# 88E1512_1000M_SFP.net
KiCad netlist of a schematic drawn in Altium Designer
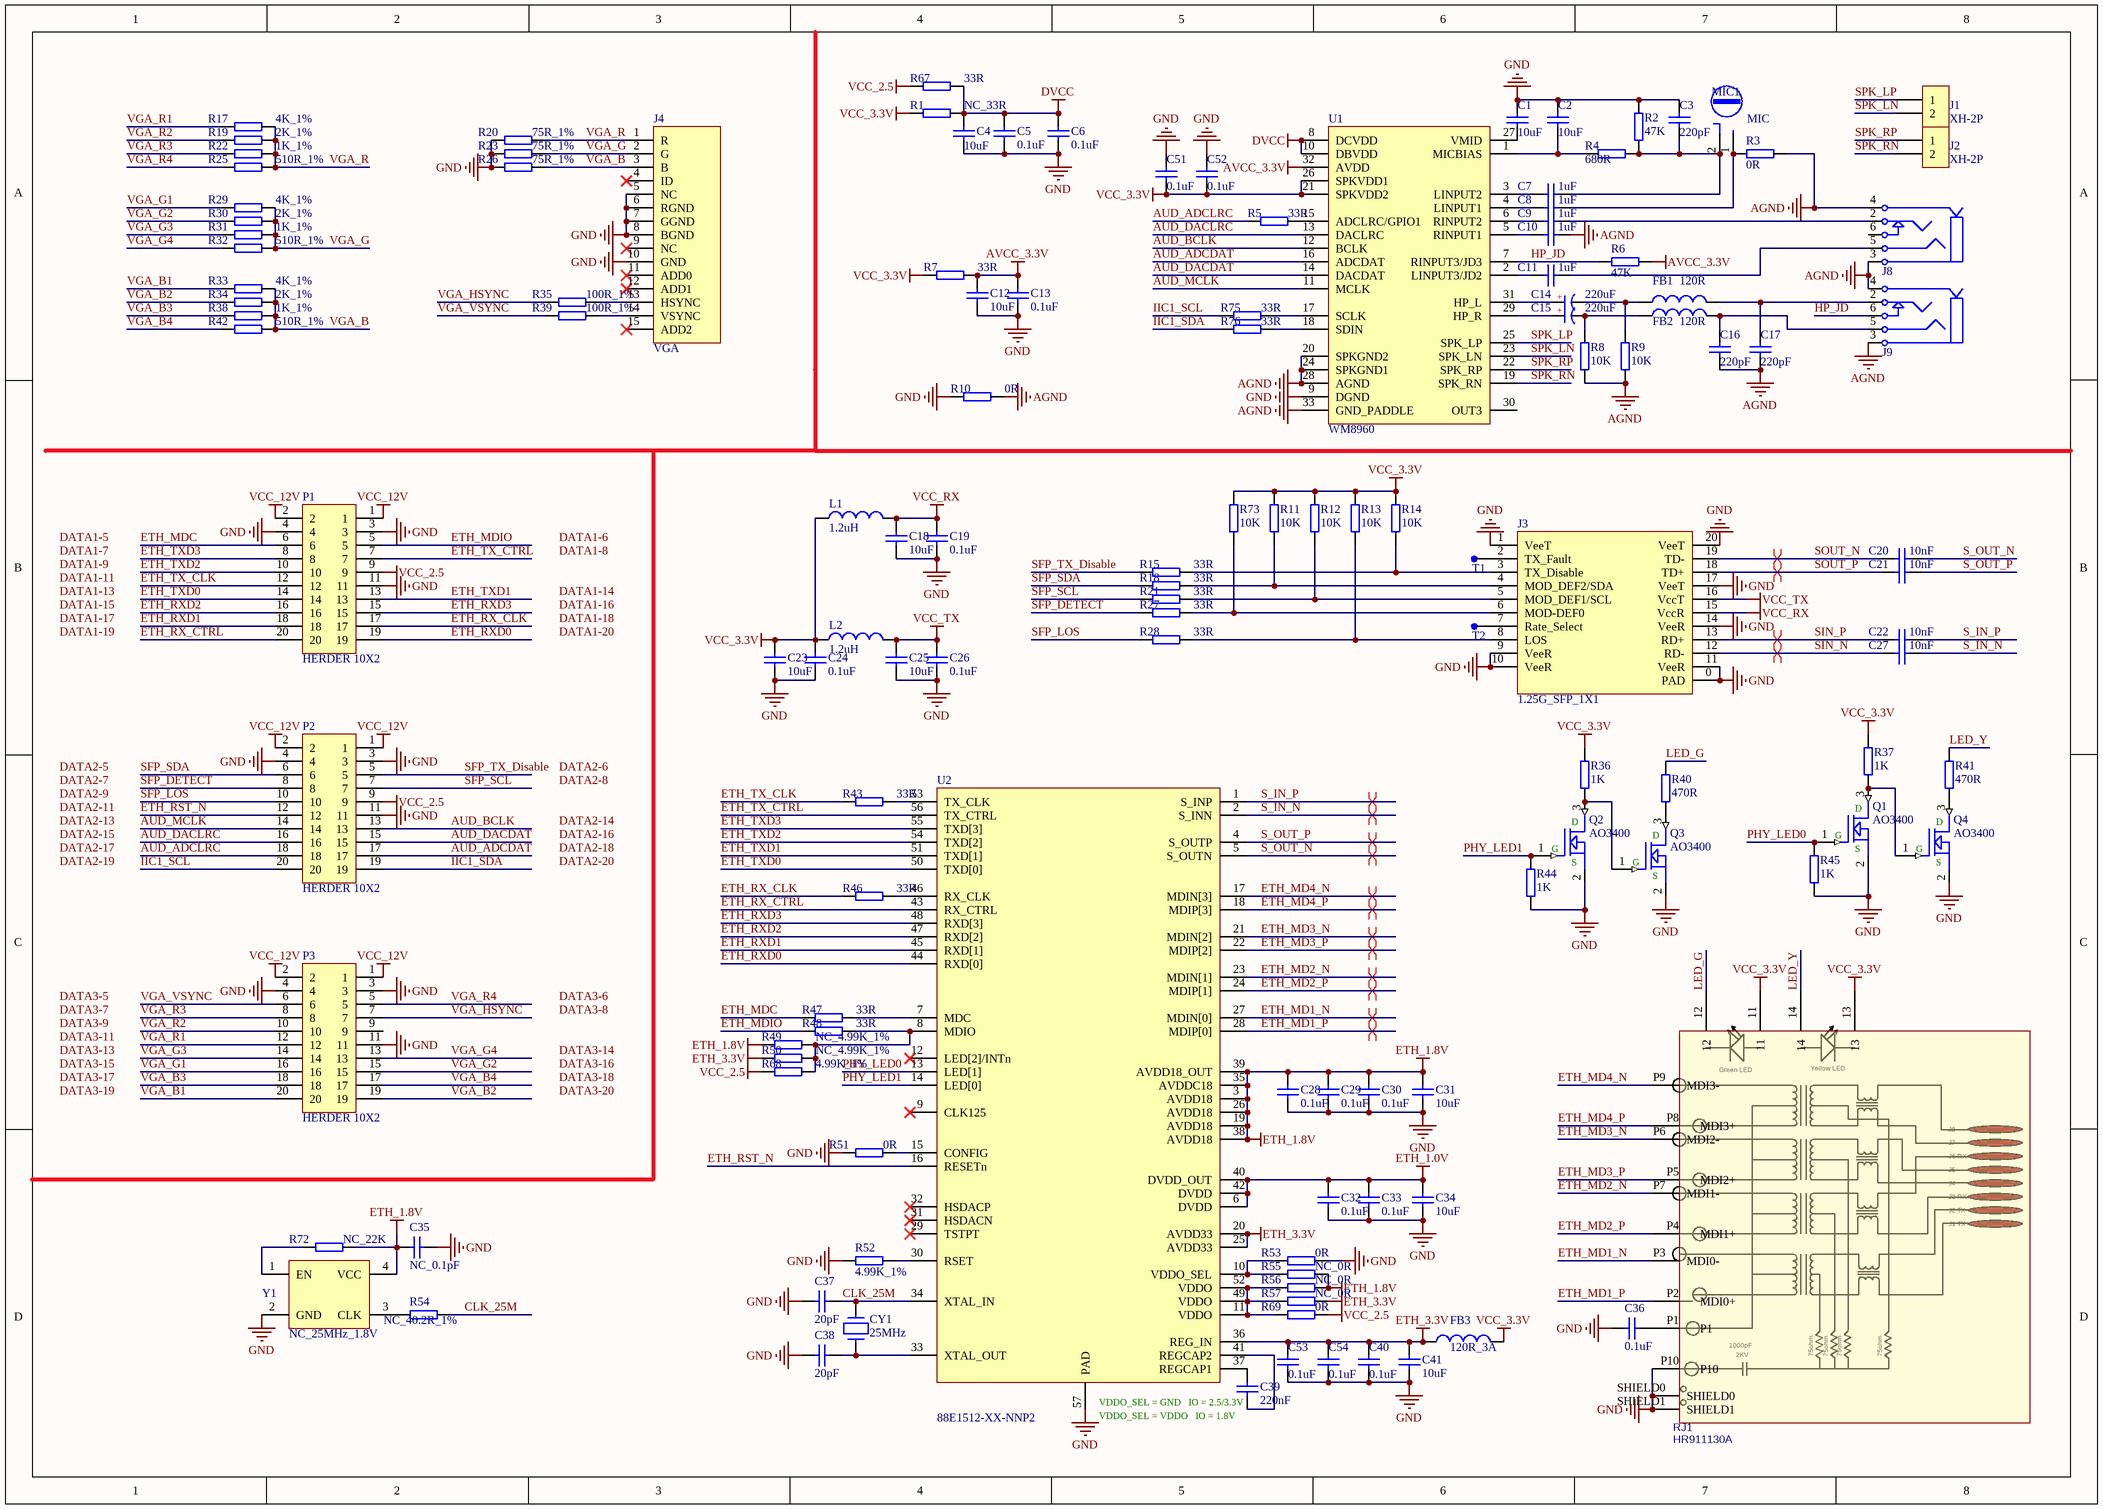
[diagram p0: 88E1512_1000M_SFP.SchDoc]

(export (version "E")
  (design (tool "Eeschema 10.0.6"))
  (components
    (comp (ref "C1")
      (value "CC41-0603-22pF")
      (footprint "0402C")
      (description "NPO贴片电容")
      (fields (field (name "ALTIUM_UNNAMED_1") "10uF"))
      (libsource (lib "我的元件库") (part "CC41-0603-22pF"))
    )
    (comp (ref "C2")
      (value "CC41-0603-22pF")
      (footprint "0402C")
      (description "NPO贴片电容")
      (fields (field (name "ALTIUM_UNNAMED_1") "10uF"))
      (libsource (lib "我的元件库") (part "CC41-0603-22pF"))
    )
    (comp (ref "C3")
      (value "CC41-0603-22pF")
      (footprint "0402C")
      (description "NPO贴片电容")
      (fields (field (name "ALTIUM_UNNAMED_1") "220pF"))
      (libsource (lib "我的元件库") (part "CC41-0603-22pF"))
    )
    (comp (ref "C4")
      (value "10uF")
      (footprint "0402C")
      (description "NPO贴片电容")
      (libsource (lib "我的元件库") (part "CC41-0603-22pF"))
    )
    (comp (ref "C5")
      (value "CC41-0603-22pF")
      (footprint "0402C")
      (description "NPO贴片电容")
      (fields (field (name "ALTIUM_UNNAMED_1") "0.1uF"))
      (libsource (lib "我的元件库") (part "CC41-0603-22pF"))
    )
    (comp (ref "C6")
      (value "CC41-0603-22pF")
      (footprint "0402C")
      (description "NPO贴片电容")
      (fields (field (name "ALTIUM_UNNAMED_1") "0.1uF"))
      (libsource (lib "我的元件库") (part "CC41-0603-22pF"))
    )
    (comp (ref "C7")
      (value "CC41-0603-22pF")
      (footprint "0402C")
      (description "NPO贴片电容")
      (fields (field (name "ALTIUM_UNNAMED_1") "1uF"))
      (libsource (lib "我的元件库") (part "CC41-0603-22pF"))
    )
    (comp (ref "C8")
      (value "CC41-0603-22pF")
      (footprint "0402C")
      (description "NPO贴片电容")
      (fields (field (name "ALTIUM_UNNAMED_1") "1uF"))
      (libsource (lib "我的元件库") (part "CC41-0603-22pF"))
    )
    (comp (ref "C9")
      (value "CC41-0603-22pF")
      (footprint "0402C")
      (description "NPO贴片电容")
      (fields (field (name "ALTIUM_UNNAMED_1") "1uF"))
      (libsource (lib "我的元件库") (part "CC41-0603-22pF"))
    )
    (comp (ref "C10")
      (value "CC41-0603-22pF")
      (footprint "0402C")
      (description "NPO贴片电容")
      (fields (field (name "ALTIUM_UNNAMED_1") "1uF"))
      (libsource (lib "我的元件库") (part "CC41-0603-22pF"))
    )
    (comp (ref "C11")
      (value "CC41-0603-22pF")
      (footprint "0402C")
      (description "NPO贴片电容")
      (fields (field (name "ALTIUM_UNNAMED_1") "1uF"))
      (libsource (lib "我的元件库") (part "CC41-0603-22pF"))
    )
    (comp (ref "C12")
      (value "CC41-0603-22pF")
      (footprint "0402C")
      (description "NPO贴片电容")
      (fields (field (name "ALTIUM_UNNAMED_1") "10uF"))
      (libsource (lib "我的元件库") (part "CC41-0603-22pF"))
    )
    (comp (ref "C13")
      (value "CC41-0603-22pF")
      (footprint "0402C")
      (description "NPO贴片电容")
      (fields (field (name "ALTIUM_UNNAMED_1") "0.1uF"))
      (libsource (lib "我的元件库") (part "CC41-0603-22pF"))
    )
    (comp (ref "C14")
      (value "220uF")
      (footprint "CM D(6.3*5.4)")
      (description "贴片电解电容")
      (fields (field (name "版权归属") "源创客"))
      (libsource (lib "ZYNQ领航者底板") (part "C-CM"))
    )
    (comp (ref "C15")
      (value "220uF")
      (footprint "CM D(6.3*5.4)")
      (description "贴片电解电容")
      (fields (field (name "版权归属") "源创客"))
      (libsource (lib "ZYNQ领航者底板") (part "C-CM"))
    )
    (comp (ref "C16")
      (value "CC41-0603-22pF")
      (footprint "0402C")
      (description "NPO贴片电容")
      (fields (field (name "ALTIUM_UNNAMED_1") "220pF"))
      (libsource (lib "我的元件库") (part "CC41-0603-22pF"))
    )
    (comp (ref "C17")
      (value "CC41-0603-22pF")
      (footprint "0402C")
      (description "NPO贴片电容")
      (fields (field (name "ALTIUM_UNNAMED_1") "220pF"))
      (libsource (lib "我的元件库") (part "CC41-0603-22pF"))
    )
    (comp (ref "C18")
      (value "CC41-0603-22pF")
      (footprint "0402C")
      (description "NPO贴片电容")
      (fields (field (name "ALTIUM_UNNAMED_1") "10uF"))
      (libsource (lib "我的元件库") (part "CC41-0603-22pF"))
    )
    (comp (ref "C19")
      (value "CC41-0603-22pF")
      (footprint "0402C")
      (description "NPO贴片电容")
      (fields (field (name "ALTIUM_UNNAMED_1") "0.1uF"))
      (libsource (lib "我的元件库") (part "CC41-0603-22pF"))
    )
    (comp (ref "C20")
      (value "10nF")
      (footprint "0402C")
      (description "NPO贴片电容")
      (libsource (lib "我的元件库") (part "CC41-0603-22pF"))
    )
    (comp (ref "C21")
      (value "10nF")
      (footprint "0402C")
      (description "NPO贴片电容")
      (libsource (lib "我的元件库") (part "CC41-0603-22pF"))
    )
    (comp (ref "C22")
      (value "10nF")
      (footprint "0402C")
      (description "NPO贴片电容")
      (libsource (lib "我的元件库") (part "CC41-0603-22pF"))
    )
    (comp (ref "C23")
      (value "CC41-0603-22pF")
      (footprint "0402C")
      (description "NPO贴片电容")
      (fields (field (name "ALTIUM_UNNAMED_1") "10uF"))
      (libsource (lib "我的元件库") (part "CC41-0603-22pF"))
    )
    (comp (ref "C24")
      (value "CC41-0603-22pF")
      (footprint "0402C")
      (description "NPO贴片电容")
      (fields (field (name "ALTIUM_UNNAMED_1") "0.1uF"))
      (libsource (lib "我的元件库") (part "CC41-0603-22pF"))
    )
    (comp (ref "C25")
      (value "CC41-0603-22pF")
      (footprint "0402C")
      (description "NPO贴片电容")
      (fields (field (name "ALTIUM_UNNAMED_1") "10uF"))
      (libsource (lib "我的元件库") (part "CC41-0603-22pF"))
    )
    (comp (ref "C26")
      (value "CC41-0603-22pF")
      (footprint "0402C")
      (description "NPO贴片电容")
      (fields (field (name "ALTIUM_UNNAMED_1") "0.1uF"))
      (libsource (lib "我的元件库") (part "CC41-0603-22pF"))
    )
    (comp (ref "C27")
      (value "10nF")
      (footprint "0402C")
      (description "NPO贴片电容")
      (libsource (lib "我的元件库") (part "CC41-0603-22pF"))
    )
    (comp (ref "C28")
      (value "CC41-0603-22pF")
      (footprint "0402C")
      (description "NPO贴片电容")
      (fields (field (name "ALTIUM_UNNAMED_1") "0.1uF"))
      (libsource (lib "我的元件库") (part "CC41-0603-22pF"))
    )
    (comp (ref "C29")
      (value "CC41-0603-22pF")
      (footprint "0402C")
      (description "NPO贴片电容")
      (fields (field (name "ALTIUM_UNNAMED_1") "0.1uF"))
      (libsource (lib "我的元件库") (part "CC41-0603-22pF"))
    )
    (comp (ref "C30")
      (value "CC41-0603-22pF")
      (footprint "0402C")
      (description "NPO贴片电容")
      (fields (field (name "ALTIUM_UNNAMED_1") "0.1uF"))
      (libsource (lib "我的元件库") (part "CC41-0603-22pF"))
    )
    (comp (ref "C31")
      (value "CC41-0603-22pF")
      (footprint "0402C")
      (description "NPO贴片电容")
      (fields (field (name "ALTIUM_UNNAMED_1") "10uF"))
      (libsource (lib "我的元件库") (part "CC41-0603-22pF"))
    )
    (comp (ref "C32")
      (value "CC41-0603-22pF")
      (footprint "0402C")
      (description "NPO贴片电容")
      (fields (field (name "ALTIUM_UNNAMED_1") "0.1uF"))
      (libsource (lib "我的元件库") (part "CC41-0603-22pF"))
    )
    (comp (ref "C33")
      (value "CC41-0603-22pF")
      (footprint "0402C")
      (description "NPO贴片电容")
      (fields (field (name "ALTIUM_UNNAMED_1") "0.1uF"))
      (libsource (lib "我的元件库") (part "CC41-0603-22pF"))
    )
    (comp (ref "C34")
      (value "CC41-0603-22pF")
      (footprint "0402C")
      (description "NPO贴片电容")
      (fields (field (name "ALTIUM_UNNAMED_1") "10uF"))
      (libsource (lib "我的元件库") (part "CC41-0603-22pF"))
    )
    (comp (ref "C35")
      (value "CC41-0603-22pF")
      (footprint "0402C")
      (description "NPO贴片电容")
      (fields (field (name "ALTIUM_UNNAMED_1") "NC_0.1pF"))
      (libsource (lib "我的元件库") (part "CC41-0603-22pF"))
    )
    (comp (ref "C36")
      (value "CC41-0603-22pF")
      (footprint "0402C")
      (description "NPO贴片电容")
      (fields (field (name "ALTIUM_UNNAMED_1") "0.1uF"))
      (libsource (lib "我的元件库") (part "CC41-0603-22pF"))
    )
    (comp (ref "C37")
      (value "CC41-0603-22pF")
      (footprint "0402C")
      (description "NPO贴片电容")
      (fields (field (name "ALTIUM_UNNAMED_1") "20pF"))
      (libsource (lib "我的元件库") (part "CC41-0603-22pF"))
    )
    (comp (ref "C38")
      (value "CC41-0603-22pF")
      (footprint "0402C")
      (description "NPO贴片电容")
      (fields (field (name "ALTIUM_UNNAMED_1") "20pF"))
      (libsource (lib "我的元件库") (part "CC41-0603-22pF"))
    )
    (comp (ref "C39")
      (value "CC41-0603-22pF")
      (footprint "0402C")
      (description "NPO贴片电容")
      (fields (field (name "ALTIUM_UNNAMED_1") "220nF"))
      (libsource (lib "我的元件库") (part "CC41-0603-22pF"))
    )
    (comp (ref "C40")
      (value "CC41-0603-22pF")
      (footprint "0402C")
      (description "NPO贴片电容")
      (fields (field (name "ALTIUM_UNNAMED_1") "0.1uF"))
      (libsource (lib "我的元件库") (part "CC41-0603-22pF"))
    )
    (comp (ref "C41")
      (value "CC41-0603-22pF")
      (footprint "0402C")
      (description "NPO贴片电容")
      (fields (field (name "ALTIUM_UNNAMED_1") "10uF"))
      (libsource (lib "我的元件库") (part "CC41-0603-22pF"))
    )
    (comp (ref "C51")
      (value "CC41-0603-22pF")
      (footprint "0402C")
      (description "NPO贴片电容")
      (fields (field (name "ALTIUM_UNNAMED_1") "0.1uF"))
      (libsource (lib "我的元件库") (part "CC41-0603-22pF"))
    )
    (comp (ref "C52")
      (value "CC41-0603-22pF")
      (footprint "0402C")
      (description "NPO贴片电容")
      (fields (field (name "ALTIUM_UNNAMED_1") "0.1uF"))
      (libsource (lib "我的元件库") (part "CC41-0603-22pF"))
    )
    (comp (ref "C53")
      (value "CC41-0603-22pF")
      (footprint "0402C")
      (description "NPO贴片电容")
      (fields (field (name "ALTIUM_UNNAMED_1") "0.1uF"))
      (libsource (lib "我的元件库") (part "CC41-0603-22pF"))
    )
    (comp (ref "C54")
      (value "CC41-0603-22pF")
      (footprint "0402C")
      (description "NPO贴片电容")
      (fields (field (name "ALTIUM_UNNAMED_1") "0.1uF"))
      (libsource (lib "我的元件库") (part "CC41-0603-22pF"))
    )
    (comp (ref "CY1") (value "25MHz") (footprint "HC-49S") (libsource (lib "我的元件库") (part "CRYES")))
    (comp (ref "FB1") (value "120R") (footprint "0603R") (libsource (lib "我的元件库") (part "L-4.7uH-4D28")))
    (comp (ref "FB2") (value "120R") (footprint "0603R") (libsource (lib "我的元件库") (part "L-4.7uH-4D28")))
    (comp (ref "FB3") (value "120R_3A") (footprint "0603R") (libsource (lib "我的元件库") (part "L-4.7uH-4D28")))
    (comp (ref "J1") (value "XH-2P") (footprint "DG1282") (libsource (lib "我的元件库") (part "CON2")))
    (comp (ref "J2") (value "XH-2P") (footprint "DG1282") (libsource (lib "我的元件库") (part "CON2")))
    (comp (ref "J3")
      (value "1.25G_SFP_1X1")
      (footprint "1.25G_SFP_1X1")
      (libsource (lib "我的元件库") (part "1.25G_SFP_1X1"))
    )
    (comp (ref "J4") (value "VGA") (footprint "VGA") (libsource (lib "我的元件库") (part "VGA")))
    (comp (ref "J8") (value "PJ-327A") (footprint "PJ327A") (libsource (lib "ZYNQ领航者底板") (part "PJ-327A")))
    (comp (ref "J9") (value "PJ-327A") (footprint "PJ327A") (libsource (lib "ZYNQ领航者底板") (part "PJ-327A")))
    (comp (ref "L1") (value "1.2uH") (footprint "0603R") (libsource (lib "我的元件库") (part "L-4.7uH-4D28")))
    (comp (ref "L2") (value "1.2uH") (footprint "0603R") (libsource (lib "我的元件库") (part "L-4.7uH-4D28")))
    (comp (ref "MIC1") (value "MIC") (footprint "MIC-6022") (libsource (lib "ZYNQ领航者底板") (part "MIC")))
    (comp (ref "P1")
      (value "HERDER 10X2")
      (footprint "HDR2X10_2.0")
      (libsource (lib "我的元件库_WORK") (part "HERDER 10X2"))
    )
    (comp (ref "P2")
      (value "HERDER 10X2")
      (footprint "HDR2X10_2.0")
      (libsource (lib "我的元件库_WORK") (part "HERDER 10X2"))
    )
    (comp (ref "P3")
      (value "HERDER 10X2")
      (footprint "HDR2X10_2.0")
      (libsource (lib "我的元件库_WORK") (part "HERDER 10X2"))
    )
    (comp (ref "Q1") (value "AO3400") (footprint "SOT23") (libsource (lib "我的元件库") (part "MOS-N")))
    (comp (ref "Q2") (value "AO3400") (footprint "SOT23") (libsource (lib "我的元件库") (part "MOS-N")))
    (comp (ref "Q3") (value "AO3400") (footprint "SOT23") (libsource (lib "我的元件库") (part "MOS-N")))
    (comp (ref "Q4") (value "AO3400") (footprint "SOT23") (libsource (lib "我的元件库") (part "MOS-N")))
    (comp (ref "R1") (value "NC_33R") (footprint "0402R") (libsource (lib "我的元件库") (part "RES1")))
    (comp (ref "R2") (value "47K") (footprint "0402R") (libsource (lib "我的元件库") (part "RES1")))
    (comp (ref "R3") (value "0R") (footprint "0402R") (libsource (lib "我的元件库") (part "RES1")))
    (comp (ref "R4") (value "680R") (footprint "0402R") (libsource (lib "我的元件库") (part "RES1")))
    (comp (ref "R5") (value "33R") (footprint "0402R") (libsource (lib "我的元件库") (part "RES1")))
    (comp (ref "R6") (value "47K") (footprint "0402R") (libsource (lib "我的元件库") (part "RES1")))
    (comp (ref "R7") (value "33R") (footprint "0402R") (libsource (lib "我的元件库") (part "RES1")))
    (comp (ref "R8") (value "10K") (footprint "0402R") (libsource (lib "我的元件库") (part "RES1")))
    (comp (ref "R9") (value "10K") (footprint "0402R") (libsource (lib "我的元件库") (part "RES1")))
    (comp (ref "R10") (value "0R") (footprint "0402R") (libsource (lib "我的元件库") (part "RES1")))
    (comp (ref "R11") (value "10K") (footprint "0402R") (libsource (lib "我的元件库") (part "RES1")))
    (comp (ref "R12") (value "10K") (footprint "0402R") (libsource (lib "我的元件库") (part "RES1")))
    (comp (ref "R13") (value "10K") (footprint "0402R") (libsource (lib "我的元件库") (part "RES1")))
    (comp (ref "R14") (value "10K") (footprint "0402R") (libsource (lib "我的元件库") (part "RES1")))
    (comp (ref "R15") (value "33R") (footprint "0402R") (libsource (lib "我的元件库") (part "RES1")))
    (comp (ref "R17") (value "4K_1%") (footprint "0402R") (libsource (lib "我的元件库") (part "RES1")))
    (comp (ref "R18") (value "33R") (footprint "0402R") (libsource (lib "我的元件库") (part "RES1")))
    (comp (ref "R19") (value "2K_1%") (footprint "0402R") (libsource (lib "我的元件库") (part "RES1")))
    (comp (ref "R20") (value "75R_1%") (footprint "0402R") (libsource (lib "我的元件库") (part "RES1")))
    (comp (ref "R21") (value "33R") (footprint "0402R") (libsource (lib "我的元件库") (part "RES1")))
    (comp (ref "R22") (value "1K_1%") (footprint "0402R") (libsource (lib "我的元件库") (part "RES1")))
    (comp (ref "R23") (value "75R_1%") (footprint "0402R") (libsource (lib "我的元件库") (part "RES1")))
    (comp (ref "R25") (value "510R_1%") (footprint "0402R") (libsource (lib "我的元件库") (part "RES1")))
    (comp (ref "R26") (value "75R_1%") (footprint "0402R") (libsource (lib "我的元件库") (part "RES1")))
    (comp (ref "R27") (value "33R") (footprint "0402R") (libsource (lib "我的元件库") (part "RES1")))
    (comp (ref "R28") (value "33R") (footprint "0402R") (libsource (lib "我的元件库") (part "RES1")))
    (comp (ref "R29") (value "4K_1%") (footprint "0402R") (libsource (lib "我的元件库") (part "RES1")))
    (comp (ref "R30") (value "2K_1%") (footprint "0402R") (libsource (lib "我的元件库") (part "RES1")))
    (comp (ref "R31") (value "1K_1%") (footprint "0402R") (libsource (lib "我的元件库") (part "RES1")))
    (comp (ref "R32") (value "510R_1%") (footprint "0402R") (libsource (lib "我的元件库") (part "RES1")))
    (comp (ref "R33") (value "4K_1%") (footprint "0402R") (libsource (lib "我的元件库") (part "RES1")))
    (comp (ref "R34") (value "2K_1%") (footprint "0402R") (libsource (lib "我的元件库") (part "RES1")))
    (comp (ref "R35") (value "100R_1%") (footprint "0402R") (libsource (lib "我的元件库") (part "RES1")))
    (comp (ref "R36") (value "1K") (footprint "0402R") (libsource (lib "我的元件库") (part "RES1")))
    (comp (ref "R37") (value "1K") (footprint "0402R") (libsource (lib "我的元件库") (part "RES1")))
    (comp (ref "R38") (value "1K_1%") (footprint "0402R") (libsource (lib "我的元件库") (part "RES1")))
    (comp (ref "R39") (value "100R_1%") (footprint "0402R") (libsource (lib "我的元件库") (part "RES1")))
    (comp (ref "R40") (value "470R") (footprint "0402R") (libsource (lib "我的元件库") (part "RES1")))
    (comp (ref "R41") (value "470R") (footprint "0402R") (libsource (lib "我的元件库") (part "RES1")))
    (comp (ref "R42") (value "510R_1%") (footprint "0402R") (libsource (lib "我的元件库") (part "RES1")))
    (comp (ref "R43") (value "33R") (footprint "0402R") (libsource (lib "我的元件库") (part "RES1")))
    (comp (ref "R44") (value "1K") (footprint "0402R") (libsource (lib "我的元件库") (part "RES1")))
    (comp (ref "R45") (value "1K") (footprint "0402R") (libsource (lib "我的元件库") (part "RES1")))
    (comp (ref "R46") (value "33R") (footprint "0402R") (libsource (lib "我的元件库") (part "RES1")))
    (comp (ref "R47") (value "33R") (footprint "0402R") (libsource (lib "我的元件库") (part "RES1")))
    (comp (ref "R48") (value "33R") (footprint "0402R") (libsource (lib "我的元件库") (part "RES1")))
    (comp (ref "R49") (value "NC_4.99K_1%") (footprint "0402R") (libsource (lib "我的元件库") (part "RES1")))
    (comp (ref "R50") (value "NC_4.99K_1%") (footprint "0402R") (libsource (lib "我的元件库") (part "RES1")))
    (comp (ref "R51") (value "0R") (footprint "0402R") (libsource (lib "我的元件库") (part "RES1")))
    (comp (ref "R52") (value "4.99K_1%") (footprint "0402R") (libsource (lib "我的元件库") (part "RES1")))
    (comp (ref "R53") (value "0R") (footprint "0402R") (libsource (lib "我的元件库") (part "RES1")))
    (comp (ref "R54") (value "NC_40.2R_1%") (footprint "0402R") (libsource (lib "我的元件库") (part "RES1")))
    (comp (ref "R55") (value "NC_0R") (footprint "0402R") (libsource (lib "我的元件库") (part "RES1")))
    (comp (ref "R56") (value "NC_0R") (footprint "0402R") (libsource (lib "我的元件库") (part "RES1")))
    (comp (ref "R57") (value "NC_0R") (footprint "0402R") (libsource (lib "我的元件库") (part "RES1")))
    (comp (ref "R67") (value "33R") (footprint "0402R") (libsource (lib "我的元件库") (part "RES1")))
    (comp (ref "R68") (value "4.99K_1%") (footprint "0402R") (libsource (lib "我的元件库") (part "RES1")))
    (comp (ref "R69") (value "0R") (footprint "0402R") (libsource (lib "我的元件库") (part "RES1")))
    (comp (ref "R72") (value "NC_22K") (footprint "0402R") (libsource (lib "我的元件库") (part "RES1")))
    (comp (ref "R73") (value "10K") (footprint "0402R") (libsource (lib "我的元件库") (part "RES1")))
    (comp (ref "R75") (value "33R") (footprint "0402R") (libsource (lib "我的元件库") (part "RES1")))
    (comp (ref "R76") (value "33R") (footprint "0402R") (libsource (lib "我的元件库") (part "RES1")))
    (comp (ref "RJ1")
      (value "HR911130A")
      (footprint "RJ45-TH_HR911130A")
      (fields (field (name "BOM_SUPPLIER PART") "C54408"))
      (libsource (lib "我的元件库") (part "HR911130A"))
    )
    (comp (ref "T1") (value "TEST") (footprint "TEST") (libsource (lib "我的元件库") (part "TEST")))
    (comp (ref "T2") (value "TEST") (footprint "TEST") (libsource (lib "我的元件库") (part "TEST")))
    (comp (ref "U1") (value "WM8960") (footprint "QFN32_W8960") (libsource (lib "我的元件库") (part "WM8960")))
    (comp (ref "U2")
      (value "88E1512-XX-NNP2")
      (footprint "88E1512_QFN56")
      (libsource (lib "我的元件库") (part "88E1512-XX-NNP2"))
    )
    (comp (ref "Y1")
      (value "NC_25MHz_1.8V")
      (footprint "3225")
      (description "3225 3.3V")
      (libsource (lib "我的元件库") (part "32.768KHz_3.3V"))
    )
  )
  (nets
    (net (code "1") (name "/AUD_ADCDAT") (class "Default")
      (node (ref "P2") (pin "17") (pinfunction "17_17") (pintype "passive"))
      (node (ref "U1") (pin "16") (pinfunction "ADCDAT_16") (pintype "passive"))
    )
    (net (code "2") (name "/AUD_ADCLRC") (class "Default")
      (node (ref "P2") (pin "18") (pinfunction "18_18") (pintype "passive"))
      (node (ref "R5") (pin "2") (pinfunction "2_2") (pintype "passive"))
    )
    (net (code "3") (name "/AUD_BCLK") (class "Default")
      (node (ref "P2") (pin "13") (pinfunction "13_13") (pintype "passive"))
      (node (ref "U1") (pin "12") (pinfunction "BCLK_12") (pintype "passive"))
    )
    (net (code "4") (name "/AUD_DACDAT") (class "Default")
      (node (ref "P2") (pin "15") (pinfunction "15_15") (pintype "passive"))
      (node (ref "U1") (pin "14") (pinfunction "DACDAT_14") (pintype "passive"))
    )
    (net (code "5") (name "/AUD_DACLRC") (class "Default")
      (node (ref "P2") (pin "16") (pinfunction "16_16") (pintype "passive"))
      (node (ref "U1") (pin "13") (pinfunction "DACLRC_13") (pintype "passive"))
    )
    (net (code "6") (name "/AUD_MCLK") (class "Default")
      (node (ref "P2") (pin "14") (pinfunction "14_14") (pintype "passive"))
      (node (ref "U1") (pin "11") (pinfunction "MCLK_11") (pintype "passive"))
    )
    (net (code "7") (name "/CLK_25M") (class "Default")
      (node (ref "C37") (pin "2") (pinfunction "2_2") (pintype "passive"))
      (node (ref "CY1") (pin "2") (pinfunction "2_2") (pintype "passive"))
      (node (ref "R54") (pin "2") (pinfunction "2_2") (pintype "passive"))
      (node (ref "U2") (pin "34") (pinfunction "XTAL_IN_34") (pintype "passive"))
    )
    (net (code "50") (name "/ETH_MD1_N") (class "Default")
      (node (ref "RJ1") (pin "P3") (pinfunction "MDI0-_P3") (pintype "passive"))
      (node (ref "U2") (pin "27") (pinfunction "MDIN[0]_27") (pintype "passive"))
    )
    (net (code "51") (name "/ETH_MD1_P") (class "Default")
      (node (ref "RJ1") (pin "P2") (pinfunction "MDI0+_P2") (pintype "passive"))
      (node (ref "U2") (pin "28") (pinfunction "MDIP[0]_28") (pintype "passive"))
    )
    (net (code "52") (name "/ETH_MD2_N") (class "Default")
      (node (ref "RJ1") (pin "P7") (pinfunction "MDI1-_P7") (pintype "passive"))
      (node (ref "U2") (pin "23") (pinfunction "MDIN[1]_23") (pintype "passive"))
    )
    (net (code "53") (name "/ETH_MD2_P") (class "Default")
      (node (ref "RJ1") (pin "P4") (pinfunction "MDI1+_P4") (pintype "passive"))
      (node (ref "U2") (pin "24") (pinfunction "MDIP[1]_24") (pintype "passive"))
    )
    (net (code "54") (name "/ETH_MD3_N") (class "Default")
      (node (ref "RJ1") (pin "P6") (pinfunction "MDI2-_P6") (pintype "passive"))
      (node (ref "U2") (pin "21") (pinfunction "MDIN[2]_21") (pintype "passive"))
    )
    (net (code "55") (name "/ETH_MD3_P") (class "Default")
      (node (ref "RJ1") (pin "P5") (pinfunction "MDI2+_P5") (pintype "passive"))
      (node (ref "U2") (pin "22") (pinfunction "MDIP[2]_22") (pintype "passive"))
    )
    (net (code "56") (name "/ETH_MD4_N") (class "Default")
      (node (ref "RJ1") (pin "P9") (pinfunction "MDI3-_P9") (pintype "passive"))
      (node (ref "U2") (pin "17") (pinfunction "MDIN[3]_17") (pintype "passive"))
    )
    (net (code "57") (name "/ETH_MD4_P") (class "Default")
      (node (ref "RJ1") (pin "P8") (pinfunction "MDI3+_P8") (pintype "passive"))
      (node (ref "U2") (pin "18") (pinfunction "MDIP[3]_18") (pintype "passive"))
    )
    (net (code "58") (name "/ETH_MDC") (class "Default")
      (node (ref "P1") (pin "6") (pinfunction "6_6") (pintype "passive"))
      (node (ref "R47") (pin "2") (pinfunction "2_2") (pintype "passive"))
    )
    (net (code "59") (name "/ETH_MDIO") (class "Default")
      (node (ref "P1") (pin "5") (pinfunction "5_5") (pintype "passive"))
      (node (ref "R48") (pin "2") (pinfunction "2_2") (pintype "passive"))
    )
    (net (code "60") (name "/ETH_RST_N") (class "Default")
      (node (ref "P2") (pin "12") (pinfunction "12_12") (pintype "passive"))
      (node (ref "U2") (pin "16") (pinfunction "RESETn_16") (pintype "passive"))
    )
    (net (code "61") (name "/ETH_RXD0") (class "Default")
      (node (ref "P1") (pin "19") (pinfunction "19_19") (pintype "passive"))
      (node (ref "U2") (pin "44") (pinfunction "RXD[0]_44") (pintype "passive"))
    )
    (net (code "62") (name "/ETH_RXD1") (class "Default")
      (node (ref "P1") (pin "18") (pinfunction "18_18") (pintype "passive"))
      (node (ref "U2") (pin "45") (pinfunction "RXD[1]_45") (pintype "passive"))
    )
    (net (code "63") (name "/ETH_RXD2") (class "Default")
      (node (ref "P1") (pin "16") (pinfunction "16_16") (pintype "passive"))
      (node (ref "U2") (pin "47") (pinfunction "RXD[2]_47") (pintype "passive"))
    )
    (net (code "64") (name "/ETH_RXD3") (class "Default")
      (node (ref "P1") (pin "15") (pinfunction "15_15") (pintype "passive"))
      (node (ref "U2") (pin "48") (pinfunction "RXD[3]_48") (pintype "passive"))
    )
    (net (code "65") (name "/ETH_RX_CLK") (class "Default")
      (node (ref "P1") (pin "17") (pinfunction "17_17") (pintype "passive"))
      (node (ref "R46") (pin "2") (pinfunction "2_2") (pintype "passive"))
    )
    (net (code "66") (name "/ETH_RX_CTRL") (class "Default")
      (node (ref "P1") (pin "20") (pinfunction "20_20") (pintype "passive"))
      (node (ref "U2") (pin "43") (pinfunction "RX_CTRL_43") (pintype "passive"))
    )
    (net (code "67") (name "/ETH_TXD0") (class "Default")
      (node (ref "P1") (pin "14") (pinfunction "14_14") (pintype "passive"))
      (node (ref "U2") (pin "50") (pinfunction "TXD[0]_50") (pintype "passive"))
    )
    (net (code "68") (name "/ETH_TXD1") (class "Default")
      (node (ref "P1") (pin "13") (pinfunction "13_13") (pintype "passive"))
      (node (ref "U2") (pin "51") (pinfunction "TXD[1]_51") (pintype "passive"))
    )
    (net (code "69") (name "/ETH_TXD2") (class "Default")
      (node (ref "P1") (pin "10") (pinfunction "10_10") (pintype "passive"))
      (node (ref "U2") (pin "54") (pinfunction "TXD[2]_54") (pintype "passive"))
    )
    (net (code "70") (name "/ETH_TXD3") (class "Default")
      (node (ref "P1") (pin "8") (pinfunction "8_8") (pintype "passive"))
      (node (ref "U2") (pin "55") (pinfunction "TXD[3]_55") (pintype "passive"))
    )
    (net (code "71") (name "/ETH_TX_CLK") (class "Default")
      (node (ref "P1") (pin "12") (pinfunction "12_12") (pintype "passive"))
      (node (ref "R43") (pin "2") (pinfunction "2_2") (pintype "passive"))
    )
    (net (code "72") (name "/ETH_TX_CTRL") (class "Default")
      (node (ref "P1") (pin "7") (pinfunction "7_7") (pintype "passive"))
      (node (ref "U2") (pin "56") (pinfunction "TX_CTRL_56") (pintype "passive"))
    )
    (net (code "73") (name "/HP_JD") (class "Default")
      (node (ref "J9") (pin "6") (pinfunction "6_6") (pintype "passive"))
      (node (ref "R6") (pin "1") (pinfunction "1_1") (pintype "passive"))
      (node (ref "U1") (pin "7") (pinfunction "RINPUT3/JD3_7") (pintype "passive"))
    )
    (net (code "74") (name "/IIC1_SCL") (class "Default")
      (node (ref "P2") (pin "20") (pinfunction "20_20") (pintype "passive"))
      (node (ref "R75") (pin "2") (pinfunction "2_2") (pintype "passive"))
    )
    (net (code "75") (name "/IIC1_SDA") (class "Default")
      (node (ref "P2") (pin "19") (pinfunction "19_19") (pintype "passive"))
      (node (ref "R76") (pin "2") (pinfunction "2_2") (pintype "passive"))
    )
    (net (code "76") (name "/LED_G") (class "Default")
      (node (ref "R40") (pin "1") (pinfunction "1_1") (pintype "passive"))
      (node (ref "RJ1") (pin "12") (pinfunction "12_12") (pintype "passive"))
    )
    (net (code "77") (name "/LED_Y") (class "Default")
      (node (ref "R41") (pin "1") (pinfunction "1_1") (pintype "passive"))
      (node (ref "RJ1") (pin "14") (pinfunction "14_14") (pintype "passive"))
    )
    (net (code "78") (name "/PHY_LED0") (class "Default")
      (node (ref "Q1") (pin "1") (pinfunction "1_1") (pintype "input"))
      (node (ref "R45") (pin "2") (pinfunction "2_2") (pintype "passive"))
      (node (ref "U2") (pin "13") (pinfunction "LED[1]_13") (pintype "passive"))
    )
    (net (code "79") (name "/PHY_LED1") (class "Default")
      (node (ref "Q2") (pin "1") (pinfunction "1_1") (pintype "input"))
      (node (ref "R44") (pin "2") (pinfunction "2_2") (pintype "passive"))
      (node (ref "U2") (pin "14") (pinfunction "LED[0]_14") (pintype "passive"))
    )
    (net (code "80") (name "/SFP_DETECT") (class "Default")
      (node (ref "P2") (pin "8") (pinfunction "8_8") (pintype "passive"))
      (node (ref "R27") (pin "2") (pinfunction "2_2") (pintype "passive"))
    )
    (net (code "81") (name "/SFP_LOS") (class "Default")
      (node (ref "P2") (pin "10") (pinfunction "10_10") (pintype "passive"))
      (node (ref "R28") (pin "2") (pinfunction "2_2") (pintype "passive"))
    )
    (net (code "82") (name "/SFP_SCL") (class "Default")
      (node (ref "P2") (pin "7") (pinfunction "7_7") (pintype "passive"))
      (node (ref "R21") (pin "2") (pinfunction "2_2") (pintype "passive"))
    )
    (net (code "83") (name "/SFP_SDA") (class "Default")
      (node (ref "P2") (pin "6") (pinfunction "6_6") (pintype "passive"))
      (node (ref "R18") (pin "2") (pinfunction "2_2") (pintype "passive"))
    )
    (net (code "84") (name "/SFP_TX_Disable") (class "Default")
      (node (ref "P2") (pin "5") (pinfunction "5_5") (pintype "passive"))
      (node (ref "R15") (pin "2") (pinfunction "2_2") (pintype "passive"))
    )
    (net (code "85") (name "/SIN_N") (class "Default")
      (node (ref "C27") (pin "2") (pinfunction "2_2") (pintype "passive"))
      (node (ref "J3") (pin "12") (pinfunction "RD-_12") (pintype "passive"))
    )
    (net (code "86") (name "/SIN_P") (class "Default")
      (node (ref "C22") (pin "2") (pinfunction "2_2") (pintype "passive"))
      (node (ref "J3") (pin "13") (pinfunction "RD+_13") (pintype "passive"))
    )
    (net (code "87") (name "/SOUT_N") (class "Default")
      (node (ref "C20") (pin "2") (pinfunction "2_2") (pintype "passive"))
      (node (ref "J3") (pin "19") (pinfunction "TD-_19") (pintype "passive"))
    )
    (net (code "88") (name "/SOUT_P") (class "Default")
      (node (ref "C21") (pin "2") (pinfunction "2_2") (pintype "passive"))
      (node (ref "J3") (pin "18") (pinfunction "TD+_18") (pintype "passive"))
    )
    (net (code "89") (name "/SPK_LN") (class "Default")
      (node (ref "J1") (pin "2") (pinfunction "2_2") (pintype "passive"))
      (node (ref "U1") (pin "23") (pinfunction "SPK_LN_23") (pintype "passive"))
    )
    (net (code "90") (name "/SPK_LP") (class "Default")
      (node (ref "J1") (pin "1") (pinfunction "1_1") (pintype "passive"))
      (node (ref "U1") (pin "25") (pinfunction "SPK_LP_25") (pintype "passive"))
    )
    (net (code "91") (name "/SPK_RN") (class "Default")
      (node (ref "J2") (pin "2") (pinfunction "2_2") (pintype "passive"))
      (node (ref "U1") (pin "19") (pinfunction "SPK_RN_19") (pintype "passive"))
    )
    (net (code "92") (name "/SPK_RP") (class "Default")
      (node (ref "J2") (pin "1") (pinfunction "1_1") (pintype "passive"))
      (node (ref "U1") (pin "22") (pinfunction "SPK_RP_22") (pintype "passive"))
    )
    (net (code "93") (name "/S_IN_N") (class "Default")
      (node (ref "C27") (pin "1") (pinfunction "1_1") (pintype "passive"))
      (node (ref "U2") (pin "2") (pinfunction "S_INN_2") (pintype "passive"))
    )
    (net (code "94") (name "/S_IN_P") (class "Default")
      (node (ref "C22") (pin "1") (pinfunction "1_1") (pintype "passive"))
      (node (ref "U2") (pin "1") (pinfunction "S_INP_1") (pintype "passive"))
    )
    (net (code "95") (name "/S_OUT_N") (class "Default")
      (node (ref "C20") (pin "1") (pinfunction "1_1") (pintype "passive"))
      (node (ref "U2") (pin "5") (pinfunction "S_OUTN_5") (pintype "passive"))
    )
    (net (code "96") (name "/S_OUT_P") (class "Default")
      (node (ref "C21") (pin "1") (pinfunction "1_1") (pintype "passive"))
      (node (ref "U2") (pin "4") (pinfunction "S_OUTP_4") (pintype "passive"))
    )
    (net (code "97") (name "/VGA_B") (class "Default")
      (node (ref "J4") (pin "3") (pinfunction "B_3") (pintype "passive"))
      (node (ref "R26") (pin "2") (pinfunction "2_2") (pintype "passive"))
      (node (ref "R33") (pin "1") (pinfunction "1_1") (pintype "passive"))
      (node (ref "R34") (pin "1") (pinfunction "1_1") (pintype "passive"))
      (node (ref "R38") (pin "1") (pinfunction "1_1") (pintype "passive"))
      (node (ref "R42") (pin "1") (pinfunction "1_1") (pintype "passive"))
    )
    (net (code "98") (name "/VGA_B1") (class "Default")
      (node (ref "P3") (pin "20") (pinfunction "20_20") (pintype "passive"))
      (node (ref "R33") (pin "2") (pinfunction "2_2") (pintype "passive"))
    )
    (net (code "99") (name "/VGA_B2") (class "Default")
      (node (ref "P3") (pin "19") (pinfunction "19_19") (pintype "passive"))
      (node (ref "R34") (pin "2") (pinfunction "2_2") (pintype "passive"))
    )
    (net (code "100") (name "/VGA_B3") (class "Default")
      (node (ref "P3") (pin "18") (pinfunction "18_18") (pintype "passive"))
      (node (ref "R38") (pin "2") (pinfunction "2_2") (pintype "passive"))
    )
    (net (code "101") (name "/VGA_B4") (class "Default")
      (node (ref "P3") (pin "17") (pinfunction "17_17") (pintype "passive"))
      (node (ref "R42") (pin "2") (pinfunction "2_2") (pintype "passive"))
    )
    (net (code "102") (name "/VGA_G") (class "Default")
      (node (ref "J4") (pin "2") (pinfunction "G_2") (pintype "passive"))
      (node (ref "R23") (pin "2") (pinfunction "2_2") (pintype "passive"))
      (node (ref "R29") (pin "1") (pinfunction "1_1") (pintype "passive"))
      (node (ref "R30") (pin "1") (pinfunction "1_1") (pintype "passive"))
      (node (ref "R31") (pin "1") (pinfunction "1_1") (pintype "passive"))
      (node (ref "R32") (pin "1") (pinfunction "1_1") (pintype "passive"))
    )
    (net (code "103") (name "/VGA_G1") (class "Default")
      (node (ref "P3") (pin "16") (pinfunction "16_16") (pintype "passive"))
      (node (ref "R29") (pin "2") (pinfunction "2_2") (pintype "passive"))
    )
    (net (code "104") (name "/VGA_G2") (class "Default")
      (node (ref "P3") (pin "15") (pinfunction "15_15") (pintype "passive"))
      (node (ref "R30") (pin "2") (pinfunction "2_2") (pintype "passive"))
    )
    (net (code "105") (name "/VGA_G3") (class "Default")
      (node (ref "P3") (pin "14") (pinfunction "14_14") (pintype "passive"))
      (node (ref "R31") (pin "2") (pinfunction "2_2") (pintype "passive"))
    )
    (net (code "106") (name "/VGA_G4") (class "Default")
      (node (ref "P3") (pin "13") (pinfunction "13_13") (pintype "passive"))
      (node (ref "R32") (pin "2") (pinfunction "2_2") (pintype "passive"))
    )
    (net (code "107") (name "/VGA_HSYNC") (class "Default")
      (node (ref "P3") (pin "7") (pinfunction "7_7") (pintype "passive"))
      (node (ref "R35") (pin "1") (pinfunction "1_1") (pintype "passive"))
    )
    (net (code "108") (name "/VGA_R") (class "Default")
      (node (ref "J4") (pin "1") (pinfunction "R_1") (pintype "passive"))
      (node (ref "R17") (pin "1") (pinfunction "1_1") (pintype "passive"))
      (node (ref "R19") (pin "1") (pinfunction "1_1") (pintype "passive"))
      (node (ref "R20") (pin "2") (pinfunction "2_2") (pintype "passive"))
      (node (ref "R22") (pin "1") (pinfunction "1_1") (pintype "passive"))
      (node (ref "R25") (pin "1") (pinfunction "1_1") (pintype "passive"))
    )
    (net (code "109") (name "/VGA_R1") (class "Default")
      (node (ref "P3") (pin "12") (pinfunction "12_12") (pintype "passive"))
      (node (ref "R17") (pin "2") (pinfunction "2_2") (pintype "passive"))
    )
    (net (code "110") (name "/VGA_R2") (class "Default")
      (node (ref "P3") (pin "10") (pinfunction "10_10") (pintype "passive"))
      (node (ref "R19") (pin "2") (pinfunction "2_2") (pintype "passive"))
    )
    (net (code "111") (name "/VGA_R3") (class "Default")
      (node (ref "P3") (pin "8") (pinfunction "8_8") (pintype "passive"))
      (node (ref "R22") (pin "2") (pinfunction "2_2") (pintype "passive"))
    )
    (net (code "112") (name "/VGA_R4") (class "Default")
      (node (ref "P3") (pin "5") (pinfunction "5_5") (pintype "passive"))
      (node (ref "R25") (pin "2") (pinfunction "2_2") (pintype "passive"))
    )
    (net (code "113") (name "/VGA_VSYNC") (class "Default")
      (node (ref "P3") (pin "6") (pinfunction "6_6") (pintype "passive"))
      (node (ref "R39") (pin "1") (pinfunction "1_1") (pintype "passive"))
    )
    (net (code "114") (name "AGND") (class "Default")
      (node (ref "C10") (pin "1") (pinfunction "1_1") (pintype "passive"))
      (node (ref "C16") (pin "1") (pinfunction "1_1") (pintype "passive"))
      (node (ref "C17") (pin "1") (pinfunction "1_1") (pintype "passive"))
      (node (ref "J8") (pin "3") (pinfunction "1_3") (pintype "passive"))
      (node (ref "J8") (pin "4") (pinfunction "4_4") (pintype "passive"))
      (node (ref "J9") (pin "3") (pinfunction "1_3") (pintype "passive"))
      (node (ref "J9") (pin "4") (pinfunction "4_4") (pintype "passive"))
      (node (ref "R10") (pin "1") (pinfunction "1_1") (pintype "passive"))
      (node (ref "R3") (pin "2") (pinfunction "2_2") (pintype "passive"))
      (node (ref "R8") (pin "1") (pinfunction "1_1") (pintype "passive"))
      (node (ref "R9") (pin "1") (pinfunction "1_1") (pintype "passive"))
      (node (ref "U1") (pin "20") (pinfunction "SPKGND2_20") (pintype "passive"))
      (node (ref "U1") (pin "24") (pinfunction "SPKGND1_24") (pintype "passive"))
      (node (ref "U1") (pin "28") (pinfunction "AGND_28") (pintype "passive"))
      (node (ref "U1") (pin "33") (pinfunction "GND_PADDLE_33") (pintype "passive"))
    )
    (net (code "115") (name "AVCC_3.3V") (class "Default")
      (node (ref "C12") (pin "2") (pinfunction "2_2") (pintype "passive"))
      (node (ref "C13") (pin "2") (pinfunction "2_2") (pintype "passive"))
      (node (ref "R6") (pin "2") (pinfunction "2_2") (pintype "passive"))
      (node (ref "R7") (pin "1") (pinfunction "1_1") (pintype "passive"))
      (node (ref "U1") (pin "32") (pinfunction "AVDD_32") (pintype "passive"))
    )
    (net (code "116") (name "DVCC") (class "Default")
      (node (ref "C4") (pin "2") (pinfunction "2_2") (pintype "passive"))
      (node (ref "C5") (pin "2") (pinfunction "2_2") (pintype "passive"))
      (node (ref "C6") (pin "2") (pinfunction "2_2") (pintype "passive"))
      (node (ref "R1") (pin "1") (pinfunction "1_1") (pintype "passive"))
      (node (ref "R67") (pin "1") (pinfunction "1_1") (pintype "passive"))
      (node (ref "U1") (pin "10") (pinfunction "DBVDD_10") (pintype "passive"))
      (node (ref "U1") (pin "8") (pinfunction "DCVDD_8") (pintype "passive"))
    )
    (net (code "117") (name "ETH_1.0V") (class "Default")
      (node (ref "C32") (pin "2") (pinfunction "2_2") (pintype "passive"))
      (node (ref "C33") (pin "2") (pinfunction "2_2") (pintype "passive"))
      (node (ref "C34") (pin "2") (pinfunction "2_2") (pintype "passive"))
      (node (ref "U2") (pin "40") (pinfunction "DVDD_OUT_40") (pintype "passive"))
      (node (ref "U2") (pin "42") (pinfunction "DVDD_42") (pintype "passive"))
      (node (ref "U2") (pin "6") (pinfunction "DVDD_6") (pintype "passive"))
    )
    (net (code "118") (name "ETH_1.8V") (class "Default")
      (node (ref "C28") (pin "2") (pinfunction "2_2") (pintype "passive"))
      (node (ref "C29") (pin "2") (pinfunction "2_2") (pintype "passive"))
      (node (ref "C30") (pin "2") (pinfunction "2_2") (pintype "passive"))
      (node (ref "C31") (pin "2") (pinfunction "2_2") (pintype "passive"))
      (node (ref "C35") (pin "1") (pinfunction "1_1") (pintype "passive"))
      (node (ref "R49") (pin "2") (pinfunction "2_2") (pintype "passive"))
      (node (ref "R55") (pin "2") (pinfunction "2_2") (pintype "passive"))
      (node (ref "R56") (pin "2") (pinfunction "2_2") (pintype "passive"))
      (node (ref "R72") (pin "2") (pinfunction "2_2") (pintype "passive"))
      (node (ref "U2") (pin "19") (pinfunction "AVDD18_19") (pintype "passive"))
      (node (ref "U2") (pin "26") (pinfunction "AVDD18_26") (pintype "passive"))
      (node (ref "U2") (pin "3") (pinfunction "AVDD18_3") (pintype "passive"))
      (node (ref "U2") (pin "35") (pinfunction "AVDDC18_35") (pintype "passive"))
      (node (ref "U2") (pin "38") (pinfunction "AVDD18_38") (pintype "passive"))
      (node (ref "U2") (pin "39") (pinfunction "AVDD18_OUT_39") (pintype "passive"))
      (node (ref "Y1") (pin "4") (pinfunction "VCC_4") (pintype "passive"))
    )
    (net (code "119") (name "ETH_3.3V") (class "Default")
      (node (ref "C40") (pin "2") (pinfunction "2_2") (pintype "passive"))
      (node (ref "C41") (pin "2") (pinfunction "2_2") (pintype "passive"))
      (node (ref "C53") (pin "2") (pinfunction "2_2") (pintype "passive"))
      (node (ref "C54") (pin "2") (pinfunction "2_2") (pintype "passive"))
      (node (ref "FB3") (pin "1") (pinfunction "1_1") (pintype "passive"))
      (node (ref "R50") (pin "2") (pinfunction "2_2") (pintype "passive"))
      (node (ref "R57") (pin "2") (pinfunction "2_2") (pintype "passive"))
      (node (ref "U2") (pin "20") (pinfunction "AVDD33_20") (pintype "passive"))
      (node (ref "U2") (pin "25") (pinfunction "AVDD33_25") (pintype "passive"))
      (node (ref "U2") (pin "36") (pinfunction "REG_IN_36") (pintype "passive"))
    )
    (net (code "120") (name "GND") (class "Default")
      (node (ref "C1") (pin "2") (pinfunction "2_2") (pintype "passive"))
      (node (ref "C12") (pin "1") (pinfunction "1_1") (pintype "passive"))
      (node (ref "C13") (pin "1") (pinfunction "1_1") (pintype "passive"))
      (node (ref "C18") (pin "1") (pinfunction "1_1") (pintype "passive"))
      (node (ref "C19") (pin "1") (pinfunction "1_1") (pintype "passive"))
      (node (ref "C2") (pin "2") (pinfunction "2_2") (pintype "passive"))
      (node (ref "C23") (pin "1") (pinfunction "1_1") (pintype "passive"))
      (node (ref "C24") (pin "1") (pinfunction "1_1") (pintype "passive"))
      (node (ref "C25") (pin "1") (pinfunction "1_1") (pintype "passive"))
      (node (ref "C26") (pin "1") (pinfunction "1_1") (pintype "passive"))
      (node (ref "C28") (pin "1") (pinfunction "1_1") (pintype "passive"))
      (node (ref "C29") (pin "1") (pinfunction "1_1") (pintype "passive"))
      (node (ref "C3") (pin "2") (pinfunction "2_2") (pintype "passive"))
      (node (ref "C30") (pin "1") (pinfunction "1_1") (pintype "passive"))
      (node (ref "C31") (pin "1") (pinfunction "1_1") (pintype "passive"))
      (node (ref "C32") (pin "1") (pinfunction "1_1") (pintype "passive"))
      (node (ref "C33") (pin "1") (pinfunction "1_1") (pintype "passive"))
      (node (ref "C34") (pin "1") (pinfunction "1_1") (pintype "passive"))
      (node (ref "C35") (pin "2") (pinfunction "2_2") (pintype "passive"))
      (node (ref "C36") (pin "2") (pinfunction "2_2") (pintype "passive"))
      (node (ref "C37") (pin "1") (pinfunction "1_1") (pintype "passive"))
      (node (ref "C38") (pin "1") (pinfunction "1_1") (pintype "passive"))
      (node (ref "C4") (pin "1") (pinfunction "1_1") (pintype "passive"))
      (node (ref "C40") (pin "1") (pinfunction "1_1") (pintype "passive"))
      (node (ref "C41") (pin "1") (pinfunction "1_1") (pintype "passive"))
      (node (ref "C5") (pin "1") (pinfunction "1_1") (pintype "passive"))
      (node (ref "C51") (pin "1") (pinfunction "1_1") (pintype "passive"))
      (node (ref "C52") (pin "1") (pinfunction "1_1") (pintype "passive"))
      (node (ref "C53") (pin "1") (pinfunction "1_1") (pintype "passive"))
      (node (ref "C54") (pin "1") (pinfunction "1_1") (pintype "passive"))
      (node (ref "C6") (pin "1") (pinfunction "1_1") (pintype "passive"))
      (node (ref "J3") (pin "0") (pinfunction "PAD_0") (pintype "passive"))
      (node (ref "J3") (pin "1") (pinfunction "VeeT_1") (pintype "passive"))
      (node (ref "J3") (pin "10") (pinfunction "VeeR_10") (pintype "passive"))
      (node (ref "J3") (pin "11") (pinfunction "VeeR_11") (pintype "passive"))
      (node (ref "J3") (pin "14") (pinfunction "VeeR_14") (pintype "passive"))
      (node (ref "J3") (pin "17") (pinfunction "VeeT_17") (pintype "passive"))
      (node (ref "J3") (pin "20") (pinfunction "VeeT_20") (pintype "passive"))
      (node (ref "J3") (pin "9") (pinfunction "VeeR_9") (pintype "passive"))
      (node (ref "J4") (pin "10") (pinfunction "GND_10") (pintype "passive"))
      (node (ref "J4") (pin "5") (pinfunction "NC_5") (pintype "passive"))
      (node (ref "J4") (pin "6") (pinfunction "RGND_6") (pintype "passive"))
      (node (ref "J4") (pin "7") (pinfunction "GGND_7") (pintype "passive"))
      (node (ref "J4") (pin "8") (pinfunction "BGND_8") (pintype "passive"))
      (node (ref "P1") (pin "11") (pinfunction "11_11") (pintype "passive"))
      (node (ref "P1") (pin "3") (pinfunction "3_3") (pintype "passive"))
      (node (ref "P1") (pin "4") (pinfunction "4_4") (pintype "passive"))
      (node (ref "P2") (pin "11") (pinfunction "11_11") (pintype "passive"))
      (node (ref "P2") (pin "3") (pinfunction "3_3") (pintype "passive"))
      (node (ref "P2") (pin "4") (pinfunction "4_4") (pintype "passive"))
      (node (ref "P3") (pin "11") (pinfunction "11_11") (pintype "passive"))
      (node (ref "P3") (pin "3") (pinfunction "3_3") (pintype "passive"))
      (node (ref "P3") (pin "4") (pinfunction "4_4") (pintype "passive"))
      (node (ref "Q1") (pin "2") (pinfunction "2_2") (pintype "passive"))
      (node (ref "Q2") (pin "2") (pinfunction "2_2") (pintype "passive"))
      (node (ref "Q3") (pin "2") (pinfunction "2_2") (pintype "passive"))
      (node (ref "Q4") (pin "2") (pinfunction "2_2") (pintype "passive"))
      (node (ref "R10") (pin "2") (pinfunction "2_2") (pintype "passive"))
      (node (ref "R2") (pin "1") (pinfunction "1_1") (pintype "passive"))
      (node (ref "R20") (pin "1") (pinfunction "1_1") (pintype "passive"))
      (node (ref "R23") (pin "1") (pinfunction "1_1") (pintype "passive"))
      (node (ref "R26") (pin "1") (pinfunction "1_1") (pintype "passive"))
      (node (ref "R44") (pin "1") (pinfunction "1_1") (pintype "passive"))
      (node (ref "R45") (pin "1") (pinfunction "1_1") (pintype "passive"))
      (node (ref "R51") (pin "1") (pinfunction "1_1") (pintype "passive"))
      (node (ref "R52") (pin "1") (pinfunction "1_1") (pintype "passive"))
      (node (ref "R53") (pin "2") (pinfunction "2_2") (pintype "passive"))
      (node (ref "RJ1") (pin "P10") (pinfunction "P10_P10") (pintype "passive"))
      (node (ref "RJ1") (pin "SHIELD0") (pinfunction "SHIELD0_SHIELD0") (pintype "passive"))
      (node (ref "RJ1") (pin "SHIELD1") (pinfunction "SHIELD1_SHIELD1") (pintype "passive"))
      (node (ref "U1") (pin "9") (pinfunction "DGND_9") (pintype "passive"))
      (node (ref "U2") (pin "57") (pinfunction "PAD_57") (pintype "passive"))
      (node (ref "Y1") (pin "2") (pinfunction "GND_2") (pintype "passive"))
    )
    (net (code "121") (name "Net-(C9-Pad1)") (class "Default")
      (node (ref "C9") (pin "1") (pinfunction "1_1") (pintype "passive"))
      (node (ref "J8") (pin "2") (pinfunction "2_2") (pintype "passive"))
    )
    (net (code "122") (name "Net-(C11-Pad1)") (class "Default")
      (node (ref "C11") (pin "1") (pinfunction "1_1") (pintype "passive"))
      (node (ref "J8") (pin "5") (pinfunction "5_5") (pintype "passive"))
    )
    (net (code "123") (name "Net-(C14-A)") (class "Default")
      (node (ref "C14") (pin "1") (pinfunction "A_1") (pintype "passive"))
      (node (ref "U1") (pin "31") (pinfunction "HP_L_31") (pintype "passive"))
    )
    (net (code "124") (name "Net-(C14-K)") (class "Default")
      (node (ref "C14") (pin "2") (pinfunction "K_2") (pintype "passive"))
      (node (ref "FB1") (pin "1") (pinfunction "1_1") (pintype "passive"))
      (node (ref "R9") (pin "2") (pinfunction "2_2") (pintype "passive"))
    )
    (net (code "125") (name "Net-(C15-A)") (class "Default")
      (node (ref "C15") (pin "1") (pinfunction "A_1") (pintype "passive"))
      (node (ref "U1") (pin "29") (pinfunction "HP_R_29") (pintype "passive"))
    )
    (net (code "126") (name "Net-(C15-K)") (class "Default")
      (node (ref "C15") (pin "2") (pinfunction "K_2") (pintype "passive"))
      (node (ref "FB2") (pin "1") (pinfunction "1_1") (pintype "passive"))
      (node (ref "R8") (pin "2") (pinfunction "2_2") (pintype "passive"))
    )
    (net (code "127") (name "Net-(C16-Pad2)") (class "Default")
      (node (ref "C16") (pin "2") (pinfunction "2_2") (pintype "passive"))
      (node (ref "FB2") (pin "2") (pinfunction "2_2") (pintype "passive"))
      (node (ref "J9") (pin "5") (pinfunction "5_5") (pintype "passive"))
    )
    (net (code "128") (name "Net-(C17-Pad2)") (class "Default")
      (node (ref "C17") (pin "2") (pinfunction "2_2") (pintype "passive"))
      (node (ref "FB1") (pin "2") (pinfunction "2_2") (pintype "passive"))
      (node (ref "J9") (pin "2") (pinfunction "2_2") (pintype "passive"))
    )
    (net (code "129") (name "Net-(C36-Pad1)") (class "Default")
      (node (ref "C36") (pin "1") (pinfunction "1_1") (pintype "passive"))
      (node (ref "RJ1") (pin "P1") (pinfunction "P1_P1") (pintype "passive"))
    )
    (net (code "130") (name "Net-(J3-LOS)") (class "Default")
      (node (ref "J3") (pin "8") (pinfunction "LOS_8") (pintype "passive"))
      (node (ref "R13") (pin "1") (pinfunction "1_1") (pintype "passive"))
      (node (ref "R28") (pin "1") (pinfunction "1_1") (pintype "passive"))
    )
    (net (code "131") (name "Net-(J3-MOD-DEF0)") (class "Default")
      (node (ref "J3") (pin "6") (pinfunction "MOD-DEF0_6") (pintype "passive"))
      (node (ref "R27") (pin "1") (pinfunction "1_1") (pintype "passive"))
      (node (ref "R73") (pin "1") (pinfunction "1_1") (pintype "passive"))
    )
    (net (code "132") (name "Net-(J3-MOD_DEF1{slash}SCL)") (class "Default")
      (node (ref "J3") (pin "5") (pinfunction "MOD_DEF1/SCL_5") (pintype "passive"))
      (node (ref "R12") (pin "1") (pinfunction "1_1") (pintype "passive"))
      (node (ref "R21") (pin "1") (pinfunction "1_1") (pintype "passive"))
    )
    (net (code "133") (name "Net-(J3-MOD_DEF2{slash}SDA)") (class "Default")
      (node (ref "J3") (pin "4") (pinfunction "MOD_DEF2/SDA_4") (pintype "passive"))
      (node (ref "R11") (pin "1") (pinfunction "1_1") (pintype "passive"))
      (node (ref "R18") (pin "1") (pinfunction "1_1") (pintype "passive"))
    )
    (net (code "134") (name "Net-(J3-Rate_Select)") (class "Default")
      (node (ref "J3") (pin "7") (pinfunction "Rate_Select_7") (pintype "passive"))
      (node (ref "T2") (pin "1") (pintype "passive"))
    )
    (net (code "135") (name "Net-(J3-TX_Disable)") (class "Default")
      (node (ref "J3") (pin "3") (pinfunction "TX_Disable_3") (pintype "passive"))
      (node (ref "R14") (pin "1") (pinfunction "1_1") (pintype "passive"))
      (node (ref "R15") (pin "1") (pinfunction "1_1") (pintype "passive"))
    )
    (net (code "136") (name "Net-(J3-TX_Fault)") (class "Default")
      (node (ref "J3") (pin "2") (pinfunction "TX_Fault_2") (pintype "passive"))
      (node (ref "T1") (pin "1") (pintype "passive"))
    )
    (net (code "137") (name "Net-(J4-HSYNC)") (class "Default")
      (node (ref "J4") (pin "13") (pinfunction "HSYNC_13") (pintype "passive"))
      (node (ref "R35") (pin "2") (pinfunction "2_2") (pintype "passive"))
    )
    (net (code "138") (name "Net-(J4-VSYNC)") (class "Default")
      (node (ref "J4") (pin "14") (pinfunction "VSYNC_14") (pintype "passive"))
      (node (ref "R39") (pin "2") (pinfunction "2_2") (pintype "passive"))
    )
    (net (code "139") (name "Net-(MIC1-GND)") (class "Default")
      (node (ref "C3") (pin "1") (pinfunction "1_1") (pintype "passive"))
      (node (ref "C7") (pin "1") (pinfunction "1_1") (pintype "passive"))
      (node (ref "MIC1") (pin "2") (pinfunction "GND_2") (pintype "passive"))
      (node (ref "R2") (pin "2") (pinfunction "2_2") (pintype "passive"))
      (node (ref "R4") (pin "1") (pinfunction "1_1") (pintype "passive"))
    )
    (net (code "140") (name "Net-(MIC1-VCC)") (class "Default")
      (node (ref "C8") (pin "1") (pinfunction "1_1") (pintype "passive"))
      (node (ref "MIC1") (pin "1") (pinfunction "VCC_1") (pintype "passive"))
      (node (ref "R3") (pin "1") (pinfunction "1_1") (pintype "passive"))
    )
    (net (code "141") (name "Net-(Q1-Pad3)") (class "Default")
      (node (ref "Q1") (pin "3") (pinfunction "3_3") (pintype "input"))
      (node (ref "Q4") (pin "1") (pinfunction "1_1") (pintype "input"))
      (node (ref "R37") (pin "1") (pinfunction "1_1") (pintype "passive"))
    )
    (net (code "142") (name "Net-(Q2-Pad3)") (class "Default")
      (node (ref "Q2") (pin "3") (pinfunction "3_3") (pintype "input"))
      (node (ref "Q3") (pin "1") (pinfunction "1_1") (pintype "input"))
      (node (ref "R36") (pin "1") (pinfunction "1_1") (pintype "passive"))
    )
    (net (code "143") (name "Net-(Q3-Pad3)") (class "Default")
      (node (ref "Q3") (pin "3") (pinfunction "3_3") (pintype "input"))
      (node (ref "R40") (pin "2") (pinfunction "2_2") (pintype "passive"))
    )
    (net (code "144") (name "Net-(Q4-Pad3)") (class "Default")
      (node (ref "Q4") (pin "3") (pinfunction "3_3") (pintype "input"))
      (node (ref "R41") (pin "2") (pinfunction "2_2") (pintype "passive"))
    )
    (net (code "145") (name "Net-(R56-Pad1)") (class "Default")
      (node (ref "R56") (pin "1") (pinfunction "1_1") (pintype "passive"))
      (node (ref "R57") (pin "1") (pinfunction "1_1") (pintype "passive"))
      (node (ref "R69") (pin "1") (pinfunction "1_1") (pintype "passive"))
      (node (ref "U2") (pin "11") (pinfunction "VDDO_11") (pintype "passive"))
      (node (ref "U2") (pin "49") (pinfunction "VDDO_49") (pintype "passive"))
      (node (ref "U2") (pin "52") (pinfunction "VDDO_52") (pintype "passive"))
    )
    (net (code "146") (name "Net-(U1-ADCLRC{slash}GPIO1)") (class "Default")
      (node (ref "R5") (pin "1") (pinfunction "1_1") (pintype "passive"))
      (node (ref "U1") (pin "15") (pinfunction "ADCLRC/GPIO1_15") (pintype "passive"))
    )
    (net (code "147") (name "Net-(U1-LINPUT1)") (class "Default")
      (node (ref "C8") (pin "2") (pinfunction "2_2") (pintype "passive"))
      (node (ref "U1") (pin "4") (pinfunction "LINPUT1_4") (pintype "passive"))
    )
    (net (code "148") (name "Net-(U1-LINPUT2)") (class "Default")
      (node (ref "C7") (pin "2") (pinfunction "2_2") (pintype "passive"))
      (node (ref "U1") (pin "3") (pinfunction "LINPUT2_3") (pintype "passive"))
    )
    (net (code "149") (name "Net-(U1-LINPUT3{slash}JD2)") (class "Default")
      (node (ref "C11") (pin "2") (pinfunction "2_2") (pintype "passive"))
      (node (ref "U1") (pin "2") (pinfunction "LINPUT3/JD2_2") (pintype "passive"))
    )
    (net (code "150") (name "Net-(U1-MICBIAS)") (class "Default")
      (node (ref "C2") (pin "1") (pinfunction "1_1") (pintype "passive"))
      (node (ref "R4") (pin "2") (pinfunction "2_2") (pintype "passive"))
      (node (ref "U1") (pin "1") (pinfunction "MICBIAS_1") (pintype "passive"))
    )
    (net (code "151") (name "Net-(U1-RINPUT1)") (class "Default")
      (node (ref "C10") (pin "2") (pinfunction "2_2") (pintype "passive"))
      (node (ref "U1") (pin "5") (pinfunction "RINPUT1_5") (pintype "passive"))
    )
    (net (code "152") (name "Net-(U1-RINPUT2)") (class "Default")
      (node (ref "C9") (pin "2") (pinfunction "2_2") (pintype "passive"))
      (node (ref "U1") (pin "6") (pinfunction "RINPUT2_6") (pintype "passive"))
    )
    (net (code "153") (name "Net-(U1-SCLK)") (class "Default")
      (node (ref "R75") (pin "1") (pinfunction "1_1") (pintype "passive"))
      (node (ref "U1") (pin "17") (pinfunction "SCLK_17") (pintype "passive"))
    )
    (net (code "154") (name "Net-(U1-SDIN)") (class "Default")
      (node (ref "R76") (pin "1") (pinfunction "1_1") (pintype "passive"))
      (node (ref "U1") (pin "18") (pinfunction "SDIN_18") (pintype "passive"))
    )
    (net (code "155") (name "Net-(U1-VMID)") (class "Default")
      (node (ref "C1") (pin "1") (pinfunction "1_1") (pintype "passive"))
      (node (ref "U1") (pin "27") (pinfunction "VMID_27") (pintype "passive"))
    )
    (net (code "156") (name "Net-(U2-CONFIG)") (class "Default")
      (node (ref "R51") (pin "2") (pinfunction "2_2") (pintype "passive"))
      (node (ref "U2") (pin "15") (pinfunction "CONFIG_15") (pintype "passive"))
    )
    (net (code "157") (name "Net-(U2-MDC)") (class "Default")
      (node (ref "R47") (pin "1") (pinfunction "1_1") (pintype "passive"))
      (node (ref "U2") (pin "7") (pinfunction "MDC_7") (pintype "passive"))
    )
    (net (code "158") (name "Net-(U2-MDIO)") (class "Default")
      (node (ref "R48") (pin "1") (pinfunction "1_1") (pintype "passive"))
      (node (ref "R49") (pin "1") (pinfunction "1_1") (pintype "passive"))
      (node (ref "R50") (pin "1") (pinfunction "1_1") (pintype "passive"))
      (node (ref "R68") (pin "1") (pinfunction "1_1") (pintype "passive"))
      (node (ref "U2") (pin "8") (pinfunction "MDIO_8") (pintype "passive"))
    )
    (net (code "159") (name "Net-(U2-REGCAP1)") (class "Default")
      (node (ref "C39") (pin "1") (pinfunction "1_1") (pintype "passive"))
      (node (ref "U2") (pin "37") (pinfunction "REGCAP1_37") (pintype "passive"))
    )
    (net (code "160") (name "Net-(U2-REGCAP2)") (class "Default")
      (node (ref "C39") (pin "2") (pinfunction "2_2") (pintype "passive"))
      (node (ref "U2") (pin "41") (pinfunction "REGCAP2_41") (pintype "passive"))
    )
    (net (code "161") (name "Net-(U2-RSET)") (class "Default")
      (node (ref "R52") (pin "2") (pinfunction "2_2") (pintype "passive"))
      (node (ref "U2") (pin "30") (pinfunction "RSET_30") (pintype "passive"))
    )
    (net (code "162") (name "Net-(U2-RX_CLK)") (class "Default")
      (node (ref "R46") (pin "1") (pinfunction "1_1") (pintype "passive"))
      (node (ref "U2") (pin "46") (pinfunction "RX_CLK_46") (pintype "passive"))
    )
    (net (code "163") (name "Net-(U2-TX_CLK)") (class "Default")
      (node (ref "R43") (pin "1") (pinfunction "1_1") (pintype "passive"))
      (node (ref "U2") (pin "53") (pinfunction "TX_CLK_53") (pintype "passive"))
    )
    (net (code "164") (name "Net-(U2-VDDO_SEL)") (class "Default")
      (node (ref "R53") (pin "1") (pinfunction "1_1") (pintype "passive"))
      (node (ref "R55") (pin "1") (pinfunction "1_1") (pintype "passive"))
      (node (ref "U2") (pin "10") (pinfunction "VDDO_SEL_10") (pintype "passive"))
    )
    (net (code "165") (name "Net-(U2-XTAL_OUT)") (class "Default")
      (node (ref "C38") (pin "2") (pinfunction "2_2") (pintype "passive"))
      (node (ref "CY1") (pin "1") (pinfunction "1_1") (pintype "passive"))
      (node (ref "U2") (pin "33") (pinfunction "XTAL_OUT_33") (pintype "passive"))
    )
    (net (code "166") (name "Net-(Y1-CLK)") (class "Default")
      (node (ref "R54") (pin "1") (pinfunction "1_1") (pintype "passive"))
      (node (ref "Y1") (pin "3") (pinfunction "CLK_3") (pintype "passive"))
    )
    (net (code "167") (name "Net-(Y1-EN)") (class "Default")
      (node (ref "R72") (pin "1") (pinfunction "1_1") (pintype "passive"))
      (node (ref "Y1") (pin "1") (pinfunction "EN_1") (pintype "passive"))
    )
    (net (code "168") (name "VCC_2.5") (class "Default")
      (node (ref "P1") (pin "9") (pinfunction "9_9") (pintype "passive"))
      (node (ref "P2") (pin "9") (pinfunction "9_9") (pintype "passive"))
      (node (ref "R67") (pin "2") (pinfunction "2_2") (pintype "passive"))
      (node (ref "R68") (pin "2") (pinfunction "2_2") (pintype "passive"))
      (node (ref "R69") (pin "2") (pinfunction "2_2") (pintype "passive"))
    )
    (net (code "169") (name "VCC_3.3V") (class "Default")
      (node (ref "C23") (pin "2") (pinfunction "2_2") (pintype "passive"))
      (node (ref "C24") (pin "2") (pinfunction "2_2") (pintype "passive"))
      (node (ref "C51") (pin "2") (pinfunction "2_2") (pintype "passive"))
      (node (ref "C52") (pin "2") (pinfunction "2_2") (pintype "passive"))
      (node (ref "FB3") (pin "2") (pinfunction "2_2") (pintype "passive"))
      (node (ref "L1") (pin "1") (pinfunction "1_1") (pintype "passive"))
      (node (ref "L2") (pin "1") (pinfunction "1_1") (pintype "passive"))
      (node (ref "R1") (pin "2") (pinfunction "2_2") (pintype "passive"))
      (node (ref "R11") (pin "2") (pinfunction "2_2") (pintype "passive"))
      (node (ref "R12") (pin "2") (pinfunction "2_2") (pintype "passive"))
      (node (ref "R13") (pin "2") (pinfunction "2_2") (pintype "passive"))
      (node (ref "R14") (pin "2") (pinfunction "2_2") (pintype "passive"))
      (node (ref "R36") (pin "2") (pinfunction "2_2") (pintype "passive"))
      (node (ref "R37") (pin "2") (pinfunction "2_2") (pintype "passive"))
      (node (ref "R7") (pin "2") (pinfunction "2_2") (pintype "passive"))
      (node (ref "R73") (pin "2") (pinfunction "2_2") (pintype "passive"))
      (node (ref "RJ1") (pin "11") (pinfunction "11_11") (pintype "passive"))
      (node (ref "RJ1") (pin "13") (pinfunction "13_13") (pintype "passive"))
      (node (ref "U1") (pin "21") (pinfunction "SPKVDD2_21") (pintype "passive"))
      (node (ref "U1") (pin "26") (pinfunction "SPKVDD1_26") (pintype "passive"))
    )
    (net (code "170") (name "VCC_12V") (class "Default")
      (node (ref "P1") (pin "1") (pinfunction "1_1") (pintype "passive"))
      (node (ref "P1") (pin "2") (pinfunction "2_2") (pintype "passive"))
      (node (ref "P2") (pin "1") (pinfunction "1_1") (pintype "passive"))
      (node (ref "P2") (pin "2") (pinfunction "2_2") (pintype "passive"))
      (node (ref "P3") (pin "1") (pinfunction "1_1") (pintype "passive"))
      (node (ref "P3") (pin "2") (pinfunction "2_2") (pintype "passive"))
    )
    (net (code "171") (name "VCC_RX") (class "Default")
      (node (ref "C18") (pin "2") (pinfunction "2_2") (pintype "passive"))
      (node (ref "C19") (pin "2") (pinfunction "2_2") (pintype "passive"))
      (node (ref "J3") (pin "15") (pinfunction "VccR_15") (pintype "passive"))
      (node (ref "L1") (pin "2") (pinfunction "2_2") (pintype "passive"))
    )
    (net (code "172") (name "VCC_TX") (class "Default")
      (node (ref "C25") (pin "2") (pinfunction "2_2") (pintype "passive"))
      (node (ref "C26") (pin "2") (pinfunction "2_2") (pintype "passive"))
      (node (ref "J3") (pin "16") (pinfunction "VccT_16") (pintype "passive"))
      (node (ref "L2") (pin "2") (pinfunction "2_2") (pintype "passive"))
    )
    (net (code "173") (name "unconnected-(J4-ADD0-Pad11)") (class "Default")
      (node (ref "J4") (pin "11") (pinfunction "ADD0_11") (pintype "passive+no_connect"))
    )
    (net (code "174") (name "unconnected-(J4-ADD1-Pad12)") (class "Default")
      (node (ref "J4") (pin "12") (pinfunction "ADD1_12") (pintype "passive+no_connect"))
    )
    (net (code "175") (name "unconnected-(J4-ADD2-Pad15)") (class "Default")
      (node (ref "J4") (pin "15") (pinfunction "ADD2_15") (pintype "passive+no_connect"))
    )
    (net (code "176") (name "unconnected-(J4-ID-Pad4)") (class "Default")
      (node (ref "J4") (pin "4") (pinfunction "ID_4") (pintype "passive+no_connect"))
    )
    (net (code "177") (name "unconnected-(J4-NC-Pad9)") (class "Default")
      (node (ref "J4") (pin "9") (pinfunction "NC_9") (pintype "passive+no_connect"))
    )
    (net (code "178") (name "unconnected-(J8-Pad6)") (class "Default")
      (node (ref "J8") (pin "6") (pinfunction "6_6") (pintype "passive"))
    )
    (net (code "179") (name "unconnected-(P3-Pad9)") (class "Default")
      (node (ref "P3") (pin "9") (pinfunction "9_9") (pintype "passive"))
    )
    (net (code "180") (name "unconnected-(U1-OUT3-Pad30)") (class "Default")
      (node (ref "U1") (pin "30") (pinfunction "OUT3_30") (pintype "passive"))
    )
    (net (code "181") (name "unconnected-(U2-CLK125-Pad9)") (class "Default")
      (node (ref "U2") (pin "9") (pinfunction "CLK125_9") (pintype "passive+no_connect"))
    )
    (net (code "182") (name "unconnected-(U2-HSDACN-Pad31)") (class "Default")
      (node (ref "U2") (pin "31") (pinfunction "HSDACN_31") (pintype "passive+no_connect"))
    )
    (net (code "183") (name "unconnected-(U2-HSDACP-Pad32)") (class "Default")
      (node (ref "U2") (pin "32") (pinfunction "HSDACP_32") (pintype "passive+no_connect"))
    )
    (net (code "184") (name "unconnected-(U2-LED[2]{slash}INTn-Pad12)") (class "Default")
      (node (ref "U2") (pin "12") (pinfunction "LED[2]/INTn_12") (pintype "passive+no_connect"))
    )
    (net (code "185") (name "unconnected-(U2-TSTPT-Pad29)") (class "Default")
      (node (ref "U2") (pin "29") (pinfunction "TSTPT_29") (pintype "passive+no_connect"))
    )
  )
)
